# CanTranceiver.net
KiCad netlist of a schematic drawn in Altium Designer
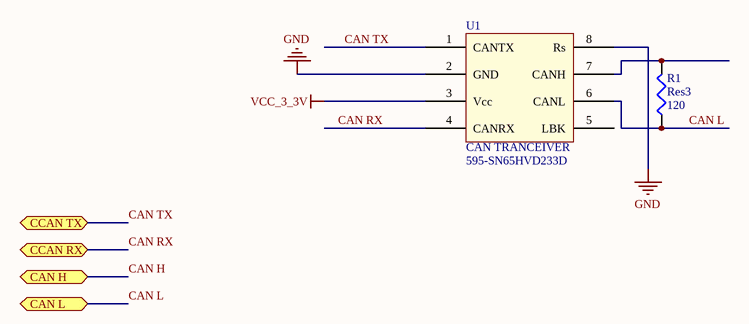
[diagram p0: CanTranceiver.SchDoc]

(export (version "E")
  (design (tool "Eeschema 10.0.6"))
  (components
    (comp (ref "R1")
      (value "Res3")
      (footprint "R0805")
      (description "Resistor")
      (fields (field (name "ALTIUM_VALUE") "120") (field (name "PUBLISHER") "Altium Limited"))
      (libsource (lib "Miscellaneous Devices") (part "Res3"))
    )
    (comp (ref "U1")
      (value "CAN TRANCEIVER")
      (footprint "SOP8")
      (fields (field (name "SUPPLIER PART NUMBER 1") "595-SN65HVD233D"))
      (libsource (lib "CAN_Node") (part "595-SN65HVD233"))
    )
  )
  (nets
    (net (code "2") (name "/CAN L") (class "Default")
      (node (ref "R1") (pin "1") (pinfunction "1_1") (pintype "passive"))
      (node (ref "U1") (pin "6") (pinfunction "CANL_6") (pintype "passive"))
    )
    (net (code "3") (name "/CAN RX") (class "Default")
      (node (ref "U1") (pin "4") (pinfunction "CANRX_4") (pintype "passive"))
    )
    (net (code "4") (name "/CAN TX") (class "Default")
      (node (ref "U1") (pin "1") (pinfunction "CANTX_1") (pintype "passive"))
    )
    (net (code "5") (name "GND") (class "Default")
      (node (ref "U1") (pin "2") (pinfunction "GND_2") (pintype "passive"))
      (node (ref "U1") (pin "8") (pinfunction "Rs_8") (pintype "passive"))
    )
    (net (code "6") (name "Net-(U1-CANH)") (class "Default")
      (node (ref "R1") (pin "2") (pinfunction "2_2") (pintype "passive"))
      (node (ref "U1") (pin "7") (pinfunction "CANH_7") (pintype "passive"))
    )
    (net (code "7") (name "VCC_3_3V") (class "Default")
      (node (ref "U1") (pin "3") (pinfunction "Vcc_3") (pintype "passive"))
    )
    (net (code "8") (name "unconnected-(U1-LBK-Pad5)") (class "Default")
      (node (ref "U1") (pin "5") (pinfunction "LBK_5") (pintype "passive"))
    )
  )
)
